# EXM_Relay_One_-_Rev_A1.net
KiCad netlist of a schematic drawn in EAGLE
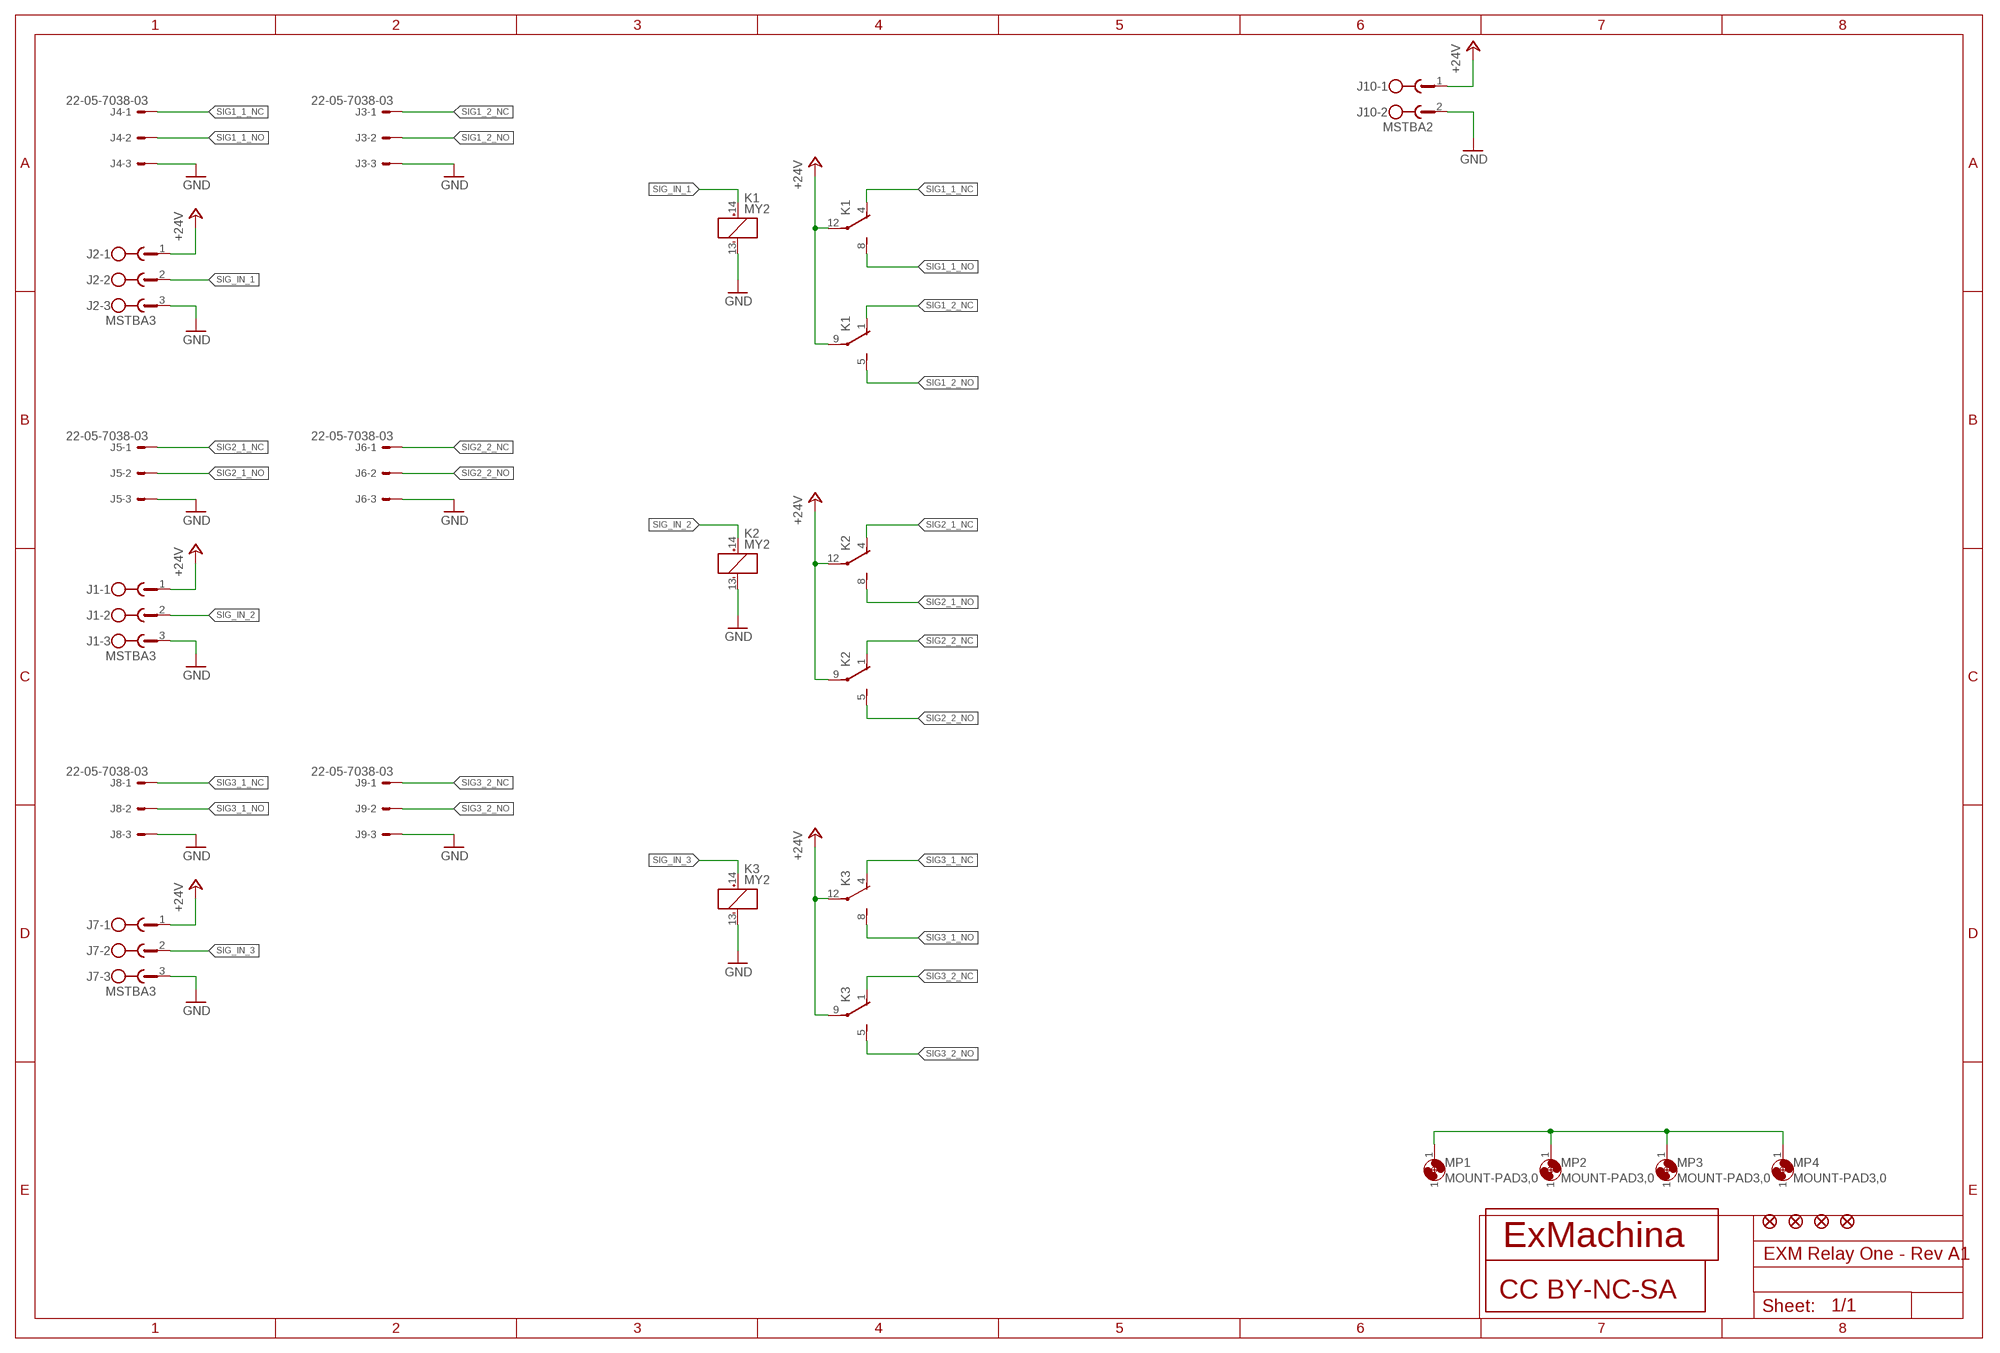
[diagram p0: schematic, sheet 1]

(export (version "E")
  (design (tool "Eeschema 10.0.6"))
  (components
    (comp (ref "CC1")
      (value "CC-BY-NC-SA")
      (footprint "eagle-import:CC-BY-NC-SA")
      (libsource (lib "eagle-import") (part "CC-BY-NC-SA"))
    )
    (comp (ref "J1")
      (value "MSTBA3")
      (footprint "eagle-import:MSTBA3")
      (fields (field (name "MF") "FARNELL") (field (name "MPN") "1757255"))
      (libsource (lib "eagle-import") (part "MSTBA3"))
    )
    (comp (ref "J2")
      (value "MSTBA3")
      (footprint "eagle-import:MSTBA3")
      (fields (field (name "MF") "FARNELL") (field (name "MPN") "1757255"))
      (libsource (lib "eagle-import") (part "MSTBA3"))
    )
    (comp (ref "J3")
      (value "22-05-7038-03")
      (footprint "eagle-import:7395-03")
      (libsource (lib "eagle-import") (part "22-?-0305-7038"))
    )
    (comp (ref "J4")
      (value "22-05-7038-03")
      (footprint "eagle-import:7395-03")
      (libsource (lib "eagle-import") (part "22-?-0305-7038"))
    )
    (comp (ref "J5")
      (value "22-05-7038-03")
      (footprint "eagle-import:7395-03")
      (libsource (lib "eagle-import") (part "22-?-0305-7038"))
    )
    (comp (ref "J6")
      (value "22-05-7038-03")
      (footprint "eagle-import:7395-03")
      (libsource (lib "eagle-import") (part "22-?-0305-7038"))
    )
    (comp (ref "J7")
      (value "MSTBA3")
      (footprint "eagle-import:MSTBA3")
      (fields (field (name "MF") "FARNELL") (field (name "MPN") "1757255"))
      (libsource (lib "eagle-import") (part "MSTBA3"))
    )
    (comp (ref "J8")
      (value "22-05-7038-03")
      (footprint "eagle-import:7395-03")
      (libsource (lib "eagle-import") (part "22-?-0305-7038"))
    )
    (comp (ref "J9")
      (value "22-05-7038-03")
      (footprint "eagle-import:7395-03")
      (libsource (lib "eagle-import") (part "22-?-0305-7038"))
    )
    (comp (ref "J10")
      (value "MSTBA2")
      (footprint "eagle-import:MSTBA2")
      (fields (field (name "MF") "FARNELL") (field (name "MPN") "1757242"))
      (libsource (lib "eagle-import") (part "MSTBA2"))
    )
    (comp (ref "JP1")
      (value "FIDUCIAL1X2")
      (footprint "eagle-import:FIDUCIAL-1X2")
      (libsource (lib "eagle-import") (part "FIDUCIAL1X2"))
    )
    (comp (ref "JP2")
      (value "FIDUCIAL1X2")
      (footprint "eagle-import:FIDUCIAL-1X2")
      (libsource (lib "eagle-import") (part "FIDUCIAL1X2"))
    )
    (comp (ref "JP3")
      (value "FIDUCIAL1X2")
      (footprint "eagle-import:FIDUCIAL-1X2")
      (libsource (lib "eagle-import") (part "FIDUCIAL1X2"))
    )
    (comp (ref "JP4")
      (value "FIDUCIAL1X2")
      (footprint "eagle-import:FIDUCIAL-1X2")
      (libsource (lib "eagle-import") (part "FIDUCIAL1X2"))
    )
    (comp (ref "K1")
      (value "MY2")
      (footprint "eagle-import:PY08")
      (libsource (lib "eagle-import") (part "MY2"))
    )
    (comp (ref "K2")
      (value "MY2")
      (footprint "eagle-import:PY08")
      (libsource (lib "eagle-import") (part "MY2"))
    )
    (comp (ref "K3")
      (value "MY2")
      (footprint "eagle-import:PY08")
      (libsource (lib "eagle-import") (part "MY2"))
    )
    (comp (ref "MP1")
      (value "MOUNT-PAD3,0")
      (footprint "eagle-import:P3,0")
      (libsource (lib "eagle-import") (part "MOUNT-PAD3,0"))
    )
    (comp (ref "MP2")
      (value "MOUNT-PAD3,0")
      (footprint "eagle-import:P3,0")
      (libsource (lib "eagle-import") (part "MOUNT-PAD3,0"))
    )
    (comp (ref "MP3")
      (value "MOUNT-PAD3,0")
      (footprint "eagle-import:P3,0")
      (libsource (lib "eagle-import") (part "MOUNT-PAD3,0"))
    )
    (comp (ref "MP4")
      (value "MOUNT-PAD3,0")
      (footprint "eagle-import:P3,0")
      (libsource (lib "eagle-import") (part "MOUNT-PAD3,0"))
    )
    (comp (ref "T1")
      (value "EXMACHINA-LOGO-NAME")
      (footprint "eagle-import:EXM-LOGO-BASELINE")
      (libsource (lib "eagle-import") (part "EXMACHINA-LOGO-NAME"))
    )
  )
  (nets
    (net (code "1") (name "+24V") (class "Default")
      (node (ref "J1") (pin "1") (pinfunction "1_1") (pintype "passive"))
      (node (ref "J10") (pin "1") (pinfunction "1_1") (pintype "passive"))
      (node (ref "J2") (pin "1") (pinfunction "1_1") (pintype "passive"))
      (node (ref "J7") (pin "1") (pinfunction "1_1") (pintype "passive"))
      (node (ref "K1") (pin "12") (pinfunction "C_12") (pintype "passive"))
      (node (ref "K1") (pin "9") (pinfunction "C_9") (pintype "passive"))
      (node (ref "K2") (pin "12") (pinfunction "C_12") (pintype "passive"))
      (node (ref "K2") (pin "9") (pinfunction "C_9") (pintype "passive"))
      (node (ref "K3") (pin "12") (pinfunction "C_12") (pintype "passive"))
      (node (ref "K3") (pin "9") (pinfunction "C_9") (pintype "passive"))
    )
    (net (code "2") (name "GND") (class "Default")
      (node (ref "J1") (pin "3") (pinfunction "1_3") (pintype "passive"))
      (node (ref "J10") (pin "2") (pinfunction "1_2") (pintype "passive"))
      (node (ref "J2") (pin "3") (pinfunction "1_3") (pintype "passive"))
      (node (ref "J3") (pin "3") (pinfunction "S_3") (pintype "passive"))
      (node (ref "J4") (pin "3") (pinfunction "S_3") (pintype "passive"))
      (node (ref "J5") (pin "3") (pinfunction "S_3") (pintype "passive"))
      (node (ref "J6") (pin "3") (pinfunction "S_3") (pintype "passive"))
      (node (ref "J7") (pin "3") (pinfunction "1_3") (pintype "passive"))
      (node (ref "J8") (pin "3") (pinfunction "S_3") (pintype "passive"))
      (node (ref "J9") (pin "3") (pinfunction "S_3") (pintype "passive"))
      (node (ref "K1") (pin "13") (pinfunction "-_13") (pintype "passive"))
      (node (ref "K2") (pin "13") (pinfunction "-_13") (pintype "passive"))
      (node (ref "K3") (pin "13") (pinfunction "-_13") (pintype "passive"))
    )
    (net (code "3") (name "MOUNT-PAD3,0") (class "Default")
      (node (ref "MP1") (pin "1") (pinfunction "1_1") (pintype "power_in"))
      (node (ref "MP2") (pin "1") (pinfunction "1_1") (pintype "power_in"))
      (node (ref "MP3") (pin "1") (pinfunction "1_1") (pintype "power_in"))
      (node (ref "MP4") (pin "1") (pinfunction "1_1") (pintype "power_in"))
    )
    (net (code "4") (name "SIG1_1_NC") (class "Default")
      (node (ref "J4") (pin "1") (pinfunction "S_1") (pintype "passive"))
      (node (ref "K1") (pin "4") (pinfunction "NC_4") (pintype "passive"))
    )
    (net (code "5") (name "SIG1_1_NO") (class "Default")
      (node (ref "J4") (pin "2") (pinfunction "S_2") (pintype "passive"))
      (node (ref "K1") (pin "8") (pinfunction "NO_8") (pintype "passive"))
    )
    (net (code "6") (name "SIG1_2_NC") (class "Default")
      (node (ref "J3") (pin "1") (pinfunction "S_1") (pintype "passive"))
      (node (ref "K1") (pin "1") (pinfunction "NC_1") (pintype "passive"))
    )
    (net (code "7") (name "SIG1_2_NO") (class "Default")
      (node (ref "J3") (pin "2") (pinfunction "S_2") (pintype "passive"))
      (node (ref "K1") (pin "5") (pinfunction "NO_5") (pintype "passive"))
    )
    (net (code "8") (name "SIG2_1_NC") (class "Default")
      (node (ref "J5") (pin "1") (pinfunction "S_1") (pintype "passive"))
      (node (ref "K2") (pin "4") (pinfunction "NC_4") (pintype "passive"))
    )
    (net (code "9") (name "SIG2_1_NO") (class "Default")
      (node (ref "J5") (pin "2") (pinfunction "S_2") (pintype "passive"))
      (node (ref "K2") (pin "8") (pinfunction "NO_8") (pintype "passive"))
    )
    (net (code "10") (name "SIG2_2_NC") (class "Default")
      (node (ref "J6") (pin "1") (pinfunction "S_1") (pintype "passive"))
      (node (ref "K2") (pin "1") (pinfunction "NC_1") (pintype "passive"))
    )
    (net (code "11") (name "SIG2_2_NO") (class "Default")
      (node (ref "J6") (pin "2") (pinfunction "S_2") (pintype "passive"))
      (node (ref "K2") (pin "5") (pinfunction "NO_5") (pintype "passive"))
    )
    (net (code "12") (name "SIG3_1_NC") (class "Default")
      (node (ref "J8") (pin "1") (pinfunction "S_1") (pintype "passive"))
      (node (ref "K3") (pin "4") (pinfunction "NC_4") (pintype "passive"))
    )
    (net (code "13") (name "SIG3_1_NO") (class "Default")
      (node (ref "J8") (pin "2") (pinfunction "S_2") (pintype "passive"))
      (node (ref "K3") (pin "8") (pinfunction "NO_8") (pintype "passive"))
    )
    (net (code "14") (name "SIG3_2_NC") (class "Default")
      (node (ref "J9") (pin "1") (pinfunction "S_1") (pintype "passive"))
      (node (ref "K3") (pin "1") (pinfunction "NC_1") (pintype "passive"))
    )
    (net (code "15") (name "SIG3_2_NO") (class "Default")
      (node (ref "J9") (pin "2") (pinfunction "S_2") (pintype "passive"))
      (node (ref "K3") (pin "5") (pinfunction "NO_5") (pintype "passive"))
    )
    (net (code "16") (name "SIG_IN_1") (class "Default")
      (node (ref "J2") (pin "2") (pinfunction "1_2") (pintype "passive"))
      (node (ref "K1") (pin "14") (pinfunction "+_14") (pintype "passive"))
    )
    (net (code "17") (name "SIG_IN_2") (class "Default")
      (node (ref "J1") (pin "2") (pinfunction "1_2") (pintype "passive"))
      (node (ref "K2") (pin "14") (pinfunction "+_14") (pintype "passive"))
    )
    (net (code "18") (name "SIG_IN_3") (class "Default")
      (node (ref "J7") (pin "2") (pinfunction "1_2") (pintype "passive"))
      (node (ref "K3") (pin "14") (pinfunction "+_14") (pintype "passive"))
    )
  )
)
